# HUI_BUI_2.net
KiCad netlist of a schematic drawn in Altium Designer
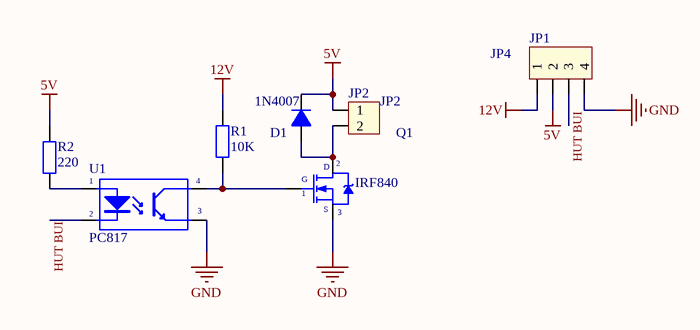
[diagram p0: HUI BUI 2.SchDoc]

(export (version "E")
  (design (tool "Eeschema 10.0.6"))
  (components
    (comp (ref "D1")
      (value "1N4007")
      (footprint "D1A")
      (description "Diode 1A")
      (libsource (lib "syhaunguyen") (part "D1A"))
    )
    (comp (ref "JP1")
      (value "JP4")
      (footprint "CON4")
      (description "Connector 4")
      (libsource (lib "syhaunguyen") (part "Con4"))
    )
    (comp (ref "JP2")
      (value "JP2")
      (footprint "CON2")
      (description "Connector 2")
      (libsource (lib "syhaunguyen") (part "Con2"))
    )
    (comp (ref "Q1")
      (value "IRF840")
      (footprint "QTO-220")
      (description "MOSFET N - CHANNEL 500V - 0.75 - 8A - TO-220")
      (libsource (lib "syhaunguyen") (part "IRF840"))
    )
    (comp (ref "R1")
      (value "10K")
      (footprint "R1/4W")
      (description "Resistor 1/4W")
      (libsource (lib "syhaunguyen") (part "R1/4W"))
    )
    (comp (ref "R2")
      (value "220")
      (footprint "R1/4W")
      (description "Resistor 1/4W")
      (libsource (lib "syhaunguyen") (part "R1/4W"))
    )
    (comp (ref "U1")
      (value "PC817")
      (footprint "DIP4/W0.3")
      (description "Single Opto")
      (libsource (lib "syhaunguyen") (part "PC817"))
    )
  )
  (nets
    (net (code "1") (name "/HUT BUI") (class "Default")
      (node (ref "JP1") (pin "3") (pinfunction "3_3") (pintype "passive"))
      (node (ref "U1") (pin "2") (pinfunction "K_2") (pintype "passive"))
    )
    (net (code "2") (name "5V") (class "Default")
      (node (ref "D1") (pin "2") (pinfunction "K_2") (pintype "passive"))
      (node (ref "JP1") (pin "2") (pinfunction "2_2") (pintype "passive"))
      (node (ref "JP2") (pin "1") (pinfunction "1_1") (pintype "passive"))
      (node (ref "R2") (pin "1") (pinfunction "1_1") (pintype "passive"))
    )
    (net (code "3") (name "12V") (class "Default")
      (node (ref "JP1") (pin "1") (pinfunction "1_1") (pintype "passive"))
      (node (ref "R1") (pin "2") (pinfunction "2_2") (pintype "passive"))
    )
    (net (code "4") (name "GND") (class "Default")
      (node (ref "JP1") (pin "4") (pinfunction "4_4") (pintype "passive"))
      (node (ref "Q1") (pin "3") (pinfunction "S_3") (pintype "passive"))
      (node (ref "U1") (pin "3") (pinfunction "E_3") (pintype "passive"))
    )
    (net (code "5") (name "Net-(D1-A)") (class "Default")
      (node (ref "D1") (pin "1") (pinfunction "A_1") (pintype "passive"))
      (node (ref "JP2") (pin "2") (pinfunction "2_2") (pintype "passive"))
      (node (ref "Q1") (pin "2") (pinfunction "D_2") (pintype "passive"))
    )
    (net (code "6") (name "Net-(Q1-G)") (class "Default")
      (node (ref "Q1") (pin "1") (pinfunction "G_1") (pintype "passive"))
      (node (ref "R1") (pin "1") (pinfunction "1_1") (pintype "passive"))
      (node (ref "U1") (pin "4") (pinfunction "C_4") (pintype "passive"))
    )
    (net (code "7") (name "Net-(U1-A)") (class "Default")
      (node (ref "R2") (pin "2") (pinfunction "2_2") (pintype "passive"))
      (node (ref "U1") (pin "1") (pinfunction "A_1") (pintype "passive"))
    )
  )
)
